# ORD_CH341A.net
KiCad netlist of a schematic drawn in Altium Designer
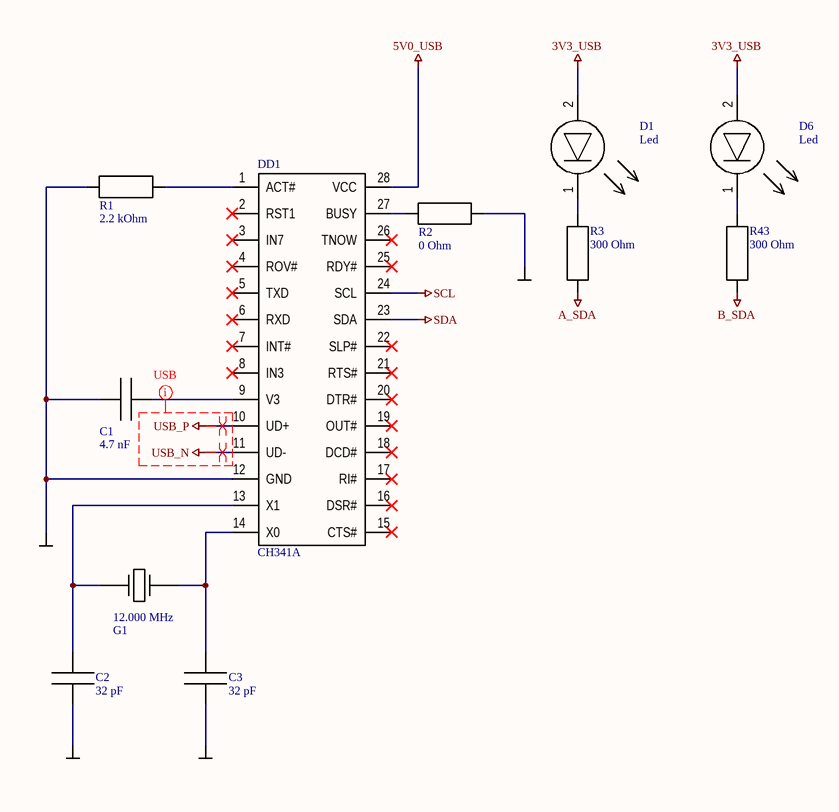
[diagram p0: ORD_CH341A.SchDoc]

(export (version "E")
  (design (tool "Eeschema 10.0.6"))
  (components
    (comp (ref "C1")
      (value "4.7 nF")
      (footprint "C0603[1608]")
      (libsource (lib "Gost_passive_lib") (part "Capacitor"))
    )
    (comp (ref "C2")
      (value "32 pF")
      (footprint "C0603[1608]")
      (libsource (lib "Gost_passive_lib") (part "Capacitor"))
    )
    (comp (ref "C3")
      (value "32 pF")
      (footprint "C0603[1608]")
      (libsource (lib "Gost_passive_lib") (part "Capacitor"))
    )
    (comp (ref "D1")
      (value "Led")
      (footprint "LED_Blue_3mm_angled")
      (libsource (lib "Gost_passive_lib") (part "Led"))
    )
    (comp (ref "D6")
      (value "Led")
      (footprint "LED_Red_3mm_angled")
      (libsource (lib "Gost_passive_lib") (part "Led"))
    )
    (comp (ref "DD1")
      (value "CH341A")
      (footprint "SOIC28")
      (description "USB Bus Convert Chip CH341A")
      (fields (field (name "MANUFACTURER_PART_NUMBER") "FV-1 Reverb IC"))
      (libsource (lib "Gost_active_libs") (part "CH341A"))
    )
    (comp (ref "G1")
      (value "12.000 MHz")
      (footprint "HC-49")
      (libsource (lib "Gost_passive_lib") (part "Crystal_2pin"))
    )
    (comp (ref "R1")
      (value "2.2 kOhm")
      (footprint "R0603[1608]")
      (libsource (lib "Gost_passive_lib") (part "Resistor"))
    )
    (comp (ref "R2")
      (value "0 Ohm")
      (footprint "R0603[1608]")
      (libsource (lib "Gost_passive_lib") (part "Resistor"))
    )
    (comp (ref "R3")
      (value "300 Ohm")
      (footprint "R0603[1608]")
      (libsource (lib "Gost_passive_lib") (part "Resistor"))
    )
    (comp (ref "R43")
      (value "300 Ohm")
      (footprint "R0603[1608]")
      (libsource (lib "Gost_passive_lib") (part "Resistor"))
    )
  )
  (nets
    (net (code "1") (name "3V3_USB") (class "Default")
      (node (ref "D1") (pin "2") (pinfunction "2_2") (pintype "passive"))
      (node (ref "D6") (pin "2") (pinfunction "2_2") (pintype "passive"))
    )
    (net (code "2") (name "5V0_USB") (class "Default")
      (node (ref "DD1") (pin "28") (pinfunction "VCC_28") (pintype "passive"))
    )
    (net (code "3") (name "A_SDA") (class "Default")
      (node (ref "R3") (pin "1") (pinfunction "1_1") (pintype "passive"))
    )
    (net (code "4") (name "B_SDA") (class "Default")
      (node (ref "R43") (pin "1") (pinfunction "1_1") (pintype "passive"))
    )
    (net (code "5") (name "GND") (class "Default")
      (node (ref "C1") (pin "1") (pinfunction "1_1") (pintype "passive"))
      (node (ref "C2") (pin "1") (pinfunction "1_1") (pintype "passive"))
      (node (ref "C3") (pin "1") (pinfunction "1_1") (pintype "passive"))
      (node (ref "DD1") (pin "12") (pinfunction "GND_12") (pintype "passive"))
      (node (ref "R1") (pin "1") (pinfunction "1_1") (pintype "passive"))
      (node (ref "R2") (pin "2") (pinfunction "2_2") (pintype "passive"))
    )
    (net (code "6") (name "Net-(D1-Pad1)") (class "Default")
      (node (ref "D1") (pin "1") (pinfunction "1_1") (pintype "passive"))
      (node (ref "R3") (pin "2") (pinfunction "2_2") (pintype "passive"))
    )
    (net (code "7") (name "Net-(D6-Pad1)") (class "Default")
      (node (ref "D6") (pin "1") (pinfunction "1_1") (pintype "passive"))
      (node (ref "R43") (pin "2") (pinfunction "2_2") (pintype "passive"))
    )
    (net (code "8") (name "Net-(DD1-ACT#)") (class "Default")
      (node (ref "DD1") (pin "1") (pinfunction "ACT#_1") (pintype "passive"))
      (node (ref "R1") (pin "2") (pinfunction "2_2") (pintype "passive"))
    )
    (net (code "9") (name "Net-(DD1-BUSY)") (class "Default")
      (node (ref "DD1") (pin "27") (pinfunction "BUSY_27") (pintype "passive"))
      (node (ref "R2") (pin "1") (pinfunction "1_1") (pintype "passive"))
    )
    (net (code "10") (name "Net-(DD1-V3)") (class "Default")
      (node (ref "C1") (pin "2") (pinfunction "2_2") (pintype "passive"))
      (node (ref "DD1") (pin "9") (pinfunction "V3_9") (pintype "passive"))
    )
    (net (code "11") (name "Net-(DD1-X0)") (class "Default")
      (node (ref "C3") (pin "2") (pinfunction "2_2") (pintype "passive"))
      (node (ref "DD1") (pin "14") (pinfunction "X0_14") (pintype "passive"))
      (node (ref "G1") (pin "2") (pinfunction "2_2") (pintype "passive"))
    )
    (net (code "12") (name "Net-(DD1-X1)") (class "Default")
      (node (ref "C2") (pin "2") (pinfunction "2_2") (pintype "passive"))
      (node (ref "DD1") (pin "13") (pinfunction "X1_13") (pintype "passive"))
      (node (ref "G1") (pin "1") (pinfunction "1_1") (pintype "passive"))
    )
    (net (code "13") (name "SCL") (class "Default")
      (node (ref "DD1") (pin "24") (pinfunction "SCL_24") (pintype "passive"))
    )
    (net (code "14") (name "SDA") (class "Default")
      (node (ref "DD1") (pin "23") (pinfunction "SDA_23") (pintype "passive"))
    )
    (net (code "15") (name "USB_N") (class "Default")
      (node (ref "DD1") (pin "11") (pinfunction "UD-_11") (pintype "passive"))
    )
    (net (code "16") (name "USB_P") (class "Default")
      (node (ref "DD1") (pin "10") (pinfunction "UD+_10") (pintype "passive"))
    )
    (net (code "17") (name "unconnected-(DD1-CTS#-Pad15)") (class "Default")
      (node (ref "DD1") (pin "15") (pinfunction "CTS#_15") (pintype "passive+no_connect"))
    )
    (net (code "18") (name "unconnected-(DD1-DCD#-Pad18)") (class "Default")
      (node (ref "DD1") (pin "18") (pinfunction "DCD#_18") (pintype "passive+no_connect"))
    )
    (net (code "19") (name "unconnected-(DD1-DSR#-Pad16)") (class "Default")
      (node (ref "DD1") (pin "16") (pinfunction "DSR#_16") (pintype "passive+no_connect"))
    )
    (net (code "20") (name "unconnected-(DD1-DTR#-Pad20)") (class "Default")
      (node (ref "DD1") (pin "20") (pinfunction "DTR#_20") (pintype "passive+no_connect"))
    )
    (net (code "21") (name "unconnected-(DD1-IN3-Pad8)") (class "Default")
      (node (ref "DD1") (pin "8") (pinfunction "IN3_8") (pintype "passive+no_connect"))
    )
    (net (code "22") (name "unconnected-(DD1-IN7-Pad3)") (class "Default")
      (node (ref "DD1") (pin "3") (pinfunction "IN7_3") (pintype "passive+no_connect"))
    )
    (net (code "23") (name "unconnected-(DD1-INT#-Pad7)") (class "Default")
      (node (ref "DD1") (pin "7") (pinfunction "INT#_7") (pintype "passive+no_connect"))
    )
    (net (code "24") (name "unconnected-(DD1-OUT#-Pad19)") (class "Default")
      (node (ref "DD1") (pin "19") (pinfunction "OUT#_19") (pintype "passive+no_connect"))
    )
    (net (code "25") (name "unconnected-(DD1-RDY#-Pad25)") (class "Default")
      (node (ref "DD1") (pin "25") (pinfunction "RDY#_25") (pintype "passive+no_connect"))
    )
    (net (code "26") (name "unconnected-(DD1-RI#-Pad17)") (class "Default")
      (node (ref "DD1") (pin "17") (pinfunction "RI#_17") (pintype "passive+no_connect"))
    )
    (net (code "27") (name "unconnected-(DD1-ROV#-Pad4)") (class "Default")
      (node (ref "DD1") (pin "4") (pinfunction "ROV#_4") (pintype "passive+no_connect"))
    )
    (net (code "28") (name "unconnected-(DD1-RST1-Pad2)") (class "Default")
      (node (ref "DD1") (pin "2") (pinfunction "RST1_2") (pintype "passive+no_connect"))
    )
    (net (code "29") (name "unconnected-(DD1-RTS#-Pad21)") (class "Default")
      (node (ref "DD1") (pin "21") (pinfunction "RTS#_21") (pintype "passive+no_connect"))
    )
    (net (code "30") (name "unconnected-(DD1-RXD-Pad6)") (class "Default")
      (node (ref "DD1") (pin "6") (pinfunction "RXD_6") (pintype "passive+no_connect"))
    )
    (net (code "31") (name "unconnected-(DD1-SLP#-Pad22)") (class "Default")
      (node (ref "DD1") (pin "22") (pinfunction "SLP#_22") (pintype "passive+no_connect"))
    )
    (net (code "32") (name "unconnected-(DD1-TNOW-Pad26)") (class "Default")
      (node (ref "DD1") (pin "26") (pinfunction "TNOW_26") (pintype "passive+no_connect"))
    )
    (net (code "33") (name "unconnected-(DD1-TXD-Pad5)") (class "Default")
      (node (ref "DD1") (pin "5") (pinfunction "TXD_5") (pintype "passive+no_connect"))
    )
  )
)
